# BMS_V3.net
KiCad netlist of a schematic drawn in Altium Designer
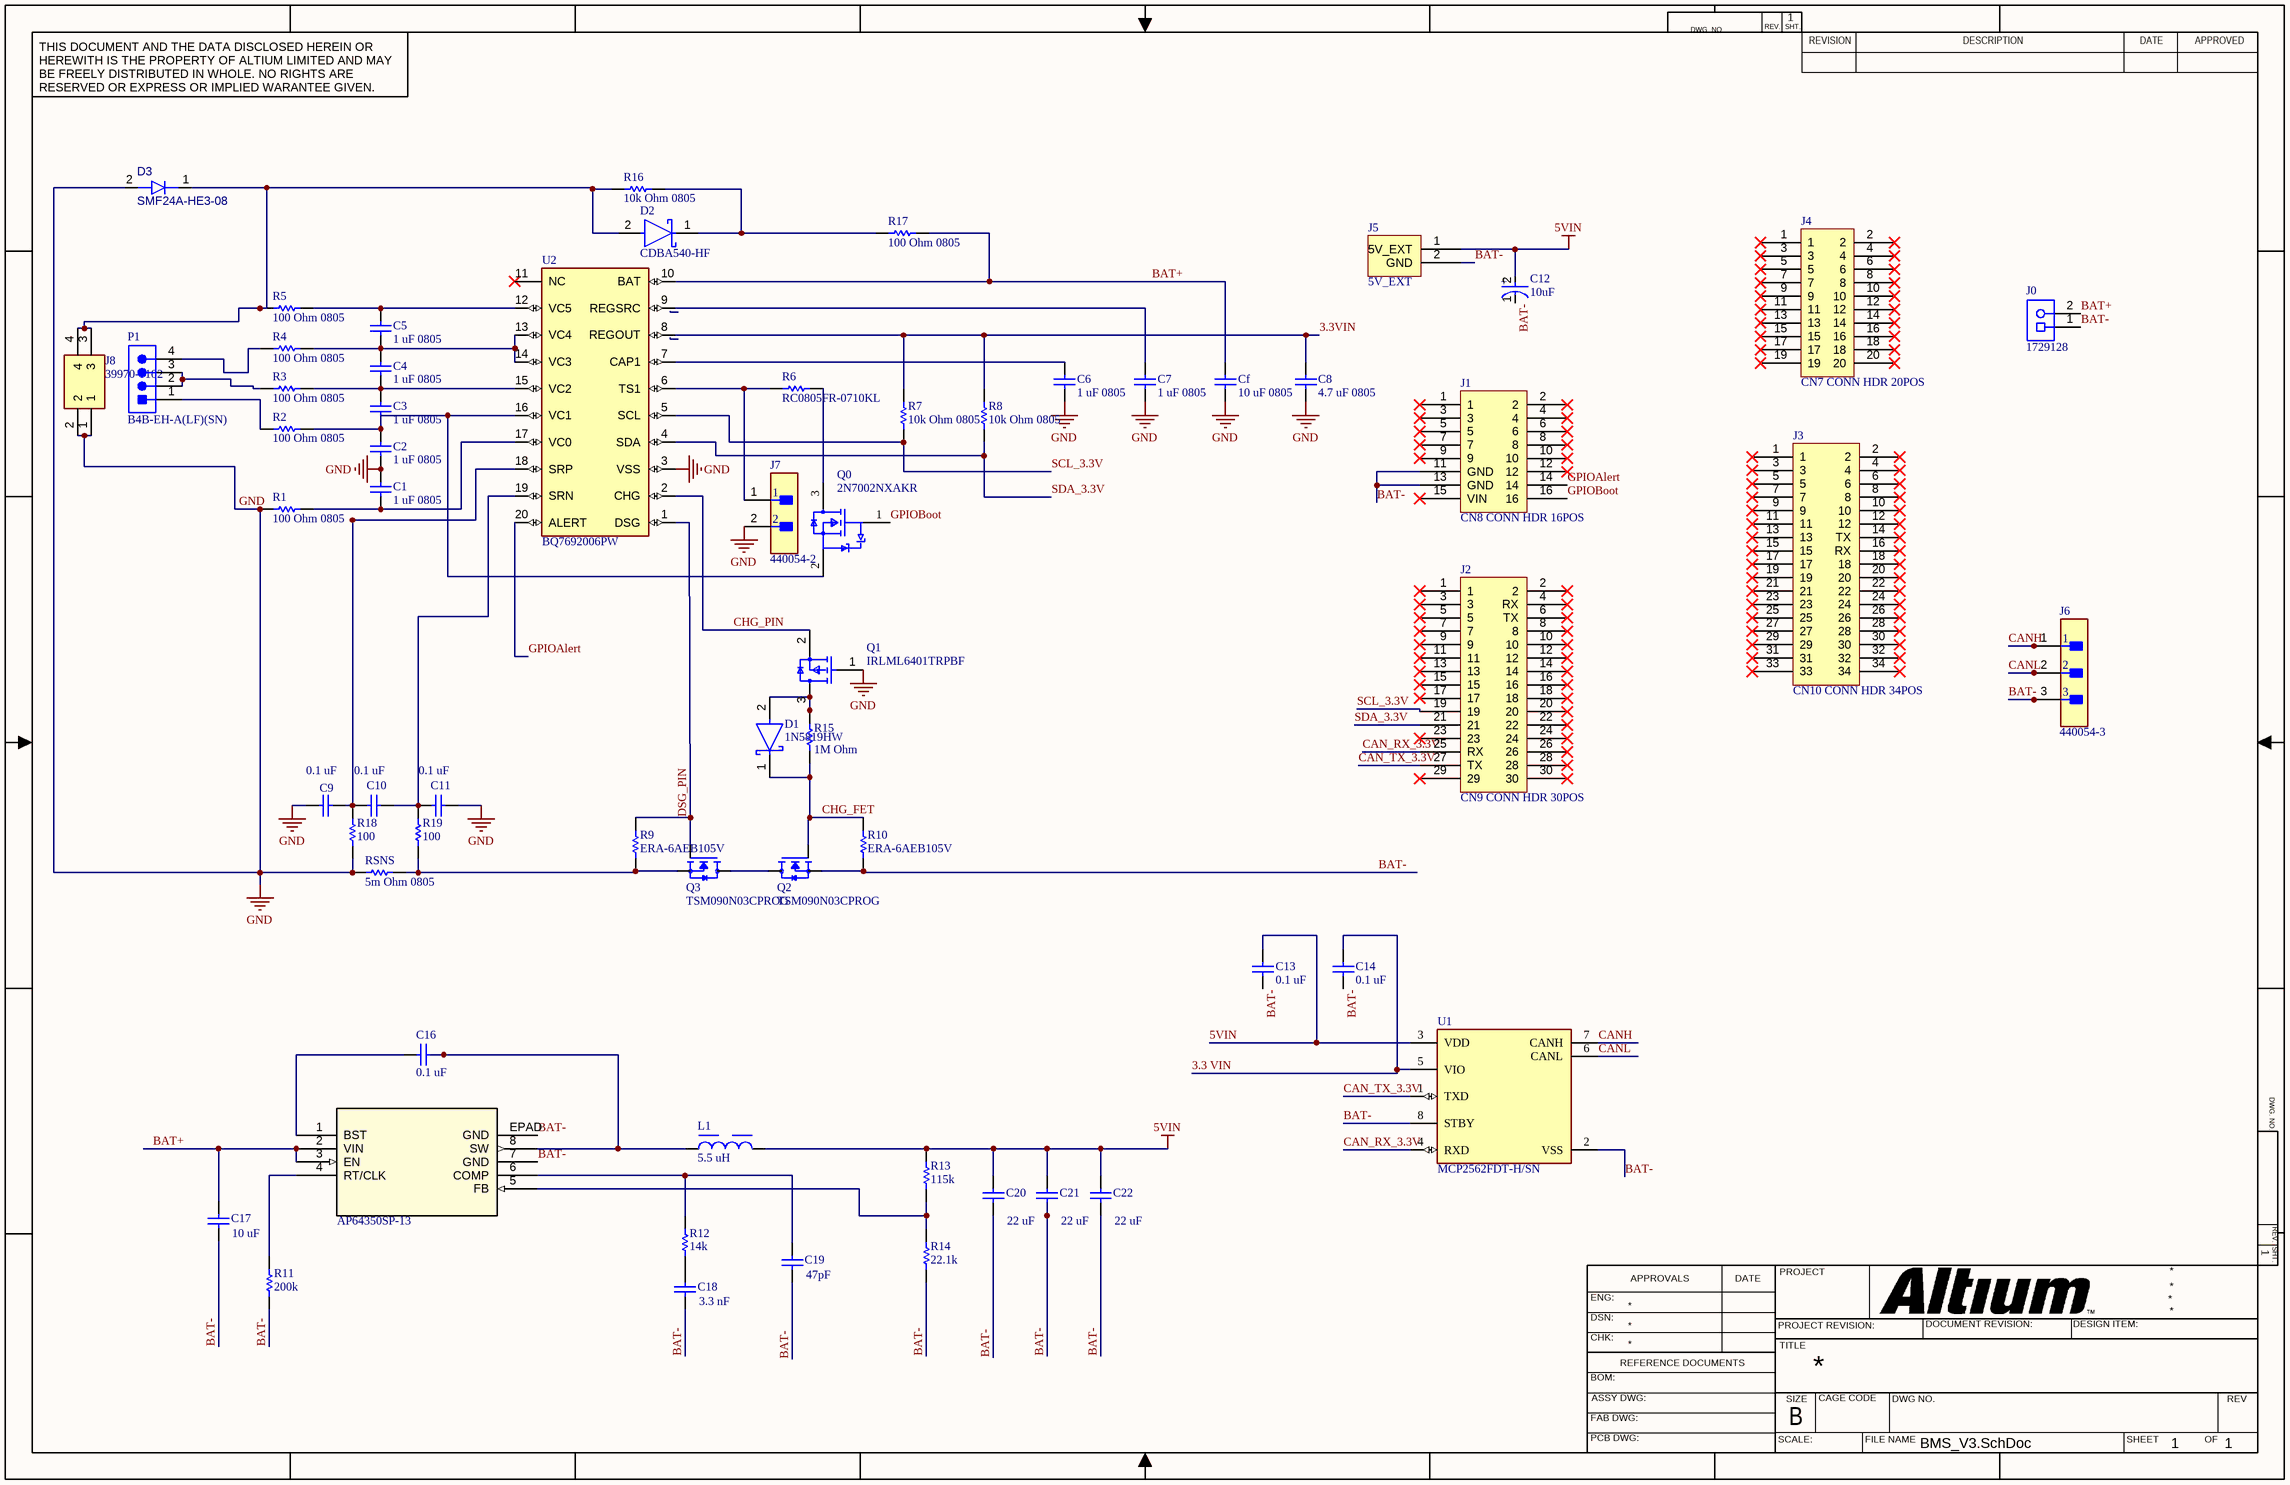
[diagram p0: BMS_V3.SchDoc]

(export (version "E")
  (design (tool "Eeschema 10.0.6"))
  (components
    (comp (ref "C1")
      (value "1 uF 0805")
      (footprint "CAPC2013X140X50LL20T25")
      (fields (field (name "PART NUMBER") "C0805C105K3RACTU") (field (name "MANUFACTURER") "Kemet"))
      (libsource (lib "Altium Content Vault") (part "CAP"))
    )
    (comp (ref "C2")
      (value "1 uF 0805")
      (footprint "CAPC2013X140X50LL20T25")
      (fields (field (name "PART NUMBER") "C0805C105K3RACTU") (field (name "MANUFACTURER") "Kemet"))
      (libsource (lib "Altium Content Vault") (part "CAP"))
    )
    (comp (ref "C3")
      (value "1 uF 0805")
      (footprint "CAPC2013X140X50LL20T25")
      (fields (field (name "PART NUMBER") "C0805C105K3RACTU") (field (name "MANUFACTURER") "Kemet"))
      (libsource (lib "Altium Content Vault") (part "CAP"))
    )
    (comp (ref "C4")
      (value "1 uF 0805")
      (footprint "CAPC2013X140X50LL20T25")
      (fields (field (name "PART NUMBER") "C0805C105K3RACTU") (field (name "MANUFACTURER") "Kemet"))
      (libsource (lib "Altium Content Vault") (part "CAP"))
    )
    (comp (ref "C5")
      (value "1 uF 0805")
      (footprint "CAPC2013X140X50LL20T25")
      (fields (field (name "PART NUMBER") "C0805C105K3RACTU") (field (name "MANUFACTURER") "Kemet"))
      (libsource (lib "Altium Content Vault") (part "CAP"))
    )
    (comp (ref "C6")
      (value "1 uF 0805")
      (footprint "CAPC2013X140X50LL20T25")
      (fields (field (name "PART NUMBER") "C0805C105K3RACTU") (field (name "MANUFACTURER") "Kemet"))
      (libsource (lib "Altium Content Vault") (part "CAP"))
    )
    (comp (ref "C7")
      (value "1 uF 0805")
      (footprint "CAPC2013X140X50LL20T25")
      (fields (field (name "PART NUMBER") "C0805C105K3RACTU") (field (name "MANUFACTURER") "Kemet"))
      (libsource (lib "Altium Content Vault") (part "CAP"))
    )
    (comp (ref "C8")
      (value "4.7 uF 0805")
      (footprint "CAPC2013X140X50LL20T25")
      (fields (field (name "PART NUMBER") "C0805C105K3RACTU") (field (name "MANUFACTURER") "Kemet"))
      (libsource (lib "Altium Content Vault") (part "CAP"))
    )
    (comp (ref "C9")
      (value "0.1 uF")
      (footprint "CAPC2013X140X50LL20T25")
      (fields (field (name "PART NUMBER") "C0805C105K3RACTU") (field (name "MANUFACTURER") "Kemet"))
      (libsource (lib "Altium Content Vault") (part "CAP"))
    )
    (comp (ref "C10")
      (value "0.1 uF")
      (footprint "CAPC2013X140X50LL20T25")
      (fields (field (name "PART NUMBER") "C0805C105K3RACTU") (field (name "MANUFACTURER") "Kemet"))
      (libsource (lib "Altium Content Vault") (part "CAP"))
    )
    (comp (ref "C11")
      (value "0.1 uF")
      (footprint "CAPC2013X140X50LL20T25")
      (fields (field (name "MANUFACTURER") "Kemet"))
      (libsource (lib "Altium Content Vault") (part "CAP"))
    )
    (comp (ref "C12")
      (value "10uF")
      (footprint "FP-FKC-MFG")
      (description "CAP ALUM 10UF 20% 50V SMD")
      (fields (field (name "TOLERANCE") "20%") (field (name "VOLTAGE") "50V"))
      (libsource (lib "Altium Content Vault") (part "a00bbbee19879c290e62620ae7e47b1"))
    )
    (comp (ref "C13")
      (value "0.1 uF")
      (footprint "CAPC2013X135X45NL10T25")
      (description "Chip Capacitor, 4.7 uF, +/- 10%, 16 V, -55 to 85 degC, 0805 (2012 Metric), RoHS, Tape and Reel")
      (fields (field (name "TOLERANCE") "10%") (field (name "PARTNUMBER") "GRM21BR61C475KA88L"))
      (libsource (lib "Altium Content Vault") (part "CAP-NP-2"))
    )
    (comp (ref "C14")
      (value "0.1 uF")
      (footprint "CAPC2013X135X45NL10T25")
      (description "Chip Capacitor, 4.7 uF, +/- 10%, 16 V, -55 to 85 degC, 0805 (2012 Metric), RoHS, Tape and Reel")
      (fields (field (name "TOLERANCE") "10%") (field (name "PARTNUMBER") "GRM21BR61C475KA88L"))
      (libsource (lib "Altium Content Vault") (part "CAP-NP-2"))
    )
    (comp (ref "C16")
      (value "0.1 uF")
      (footprint "CAPC2013X135X45NL10T25")
      (description "Chip Capacitor, 4.7 uF, +/- 10%, 16 V, -55 to 85 degC, 0805 (2012 Metric), RoHS, Tape and Reel")
      (fields (field (name "TOLERANCE") "10%") (field (name "PARTNUMBER") "GRM21BR61C475KA88L"))
      (libsource (lib "Altium Content Vault") (part "CAP-NP-2"))
    )
    (comp (ref "C17")
      (value "10 uF")
      (footprint "CAPC2013X135X45NL10T25")
      (description "Chip Capacitor, 4.7 uF, +/- 10%, 16 V, -55 to 85 degC, 0805 (2012 Metric), RoHS, Tape and Reel")
      (fields (field (name "TOLERANCE") "10%") (field (name "PARTNUMBER") "GRM21BR61C475KA88L"))
      (libsource (lib "Altium Content Vault") (part "CAP-NP-2"))
    )
    (comp (ref "C18")
      (value "3.3 nF")
      (footprint "CAPC2013X135X45NL10T25")
      (description "Chip Capacitor, 4.7 uF, +/- 10%, 16 V, -55 to 85 degC, 0805 (2012 Metric), RoHS, Tape and Reel")
      (fields (field (name "TOLERANCE") "10%") (field (name "PARTNUMBER") "GRM21BR61C475KA88L"))
      (libsource (lib "Altium Content Vault") (part "CAP-NP-2"))
    )
    (comp (ref "C19")
      (value "47pF")
      (footprint "CAPC2013X135X45NL10T25")
      (description "Chip Capacitor, 4.7 uF, +/- 10%, 16 V, -55 to 85 degC, 0805 (2012 Metric), RoHS, Tape and Reel")
      (fields (field (name "TOLERANCE") "10%") (field (name "PARTNUMBER") "GRM21BR61C475KA88L"))
      (libsource (lib "Altium Content Vault") (part "CAP-NP-2"))
    )
    (comp (ref "C20")
      (value "22 uF")
      (footprint "CAPC2013X135X45NL10T25")
      (description "Chip Capacitor, 4.7 uF, +/- 10%, 16 V, -55 to 85 degC, 0805 (2012 Metric), RoHS, Tape and Reel")
      (fields (field (name "TOLERANCE") "10%") (field (name "PARTNUMBER") "GRM21BR61C475KA88L"))
      (libsource (lib "Altium Content Vault") (part "CAP-NP-2"))
    )
    (comp (ref "C21")
      (value "22 uF")
      (footprint "CAPC2013X135X45NL10T25")
      (description "Chip Capacitor, 4.7 uF, +/- 10%, 16 V, -55 to 85 degC, 0805 (2012 Metric), RoHS, Tape and Reel")
      (fields (field (name "TOLERANCE") "10%") (field (name "PARTNUMBER") "GRM21BR61C475KA88L"))
      (libsource (lib "Altium Content Vault") (part "CAP-NP-2"))
    )
    (comp (ref "C22")
      (value "22 uF")
      (footprint "CAPC2013X135X45NL10T25")
      (description "Chip Capacitor, 4.7 uF, +/- 10%, 16 V, -55 to 85 degC, 0805 (2012 Metric), RoHS, Tape and Reel")
      (fields (field (name "TOLERANCE") "10%") (field (name "PARTNUMBER") "GRM21BR61C475KA88L"))
      (libsource (lib "Altium Content Vault") (part "CAP-NP-2"))
    )
    (comp (ref "Cf")
      (value "10 uF 0805")
      (footprint "CAPC2013X140X50LL20T25")
      (fields (field (name "PART NUMBER") "C0805C105K3RACTU") (field (name "MANUFACTURER") "Kemet"))
      (libsource (lib "Altium Content Vault") (part "CAP"))
    )
    (comp (ref "D1")
      (value "1N5819HW")
      (footprint "FP-SOD123-IPC_A")
      (description "DIODE SCHOTTKY 40V 1A SOD123")
      (libsource (lib "Altium Content Vault") (part "1d6ec82d83fb6aee721767c19dac4b9"))
    )
    (comp (ref "D2")
      (value "CDBA540-HF")
      (footprint "FP-DO-214AC-MFG")
      (description "DIODE SCHOTTKY 40V 5A DO214AC")
      (fields
        (field (name "OCTOPART") "https://octopart.com/cdba540-hf-comchip-57839773")
        (field (name "MANUFACTURER") "Comchip")
      )
      (libsource (lib "Altium Content Vault") (part "1d6ec82d83fb6aee721767c19dac4b9"))
    )
    (comp (ref "D3")
      (value "SMF24A-HE3-08")
      (footprint "DIOM2818X11N")
      (description "Trans Voltage Suppressor Diode, 1000W, 24V V(RWM), Unidirectional, 1 Element, Silicon, DO-219AB")
      (libsource (lib "Dattu Hariharan") (part "DIODE-2"))
    )
    (comp (ref "J0")
      (value "1729128")
      (footprint "PHOE-1729128-2_V")
      (description "PCB Terminal Block, 13.5 A, 400 V, 2-Pin THD, RoHS, Bulk")
      (fields (field (name "MANUFACTURER") "Phoenix Contact"))
      (libsource (lib "Altium Content Vault") (part "CN-2P-F-R2"))
    )
    (comp (ref "J1")
      (value "CN8 CONN HDR 16POS")
      (footprint "CN8_8X2_PADS")
      (description "CN8 CONN HDR 16POS 0.1 STACK")
      (libsource (lib "Dattu Hariharan") (part "CN8 CONN HDR 16POS"))
    )
    (comp (ref "J2")
      (value "CN9 CONN HDR 30POS")
      (footprint "CN9_15X2_PADS")
      (description "CN9 CONN HDR 30 POS  0.1 STACK")
      (libsource (lib "Dattu Hariharan") (part "CN9 CONN HDR 30POS"))
    )
    (comp (ref "J3")
      (value "CN10 CONN HDR 34POS")
      (footprint "CN10_17X2_PADS")
      (description "CN10 CONN HDR 34 POS  0.1 STACK")
      (libsource (lib "Dattu Hariharan") (part "CN10 CONN HDR 34POS"))
    )
    (comp (ref "J4")
      (value "CN7 CONN HDR 20POS")
      (footprint "CN7_10X2_PADS")
      (description "CN7 CONN HDR 20 POS  0.1 STACK")
      (libsource (lib "Dattu Hariharan") (part "CN7 CONN HDR 20POS"))
    )
    (comp (ref "J5")
      (value "5V_EXT")
      (footprint "5V_EXT")
      (libsource (lib "Dattu Hariharan") (part "5V_EXT"))
    )
    (comp (ref "J6")
      (value "440054-3")
      (footprint "FP-440054-3-MFG")
      (description "CONN HEADER VERT 3POS 2MM")
      (fields
        (field (name "OCTOPART") "https://octopart.com/440054-3-te+connectivity-40394845")
        (field (name "MANUFACTURER") "TE Connectivity")
      )
      (libsource (lib "Altium Content Vault") (part "0d3f023dd272f625e17a2be33dea85f"))
    )
    (comp (ref "J7")
      (value "440054-2")
      (footprint "FP-440054-2-MFG")
      (description "CONN HEADER VERT 2POS 2MM")
      (fields
        (field (name "MANUFACTURER") "TE Connectivity")
        (field (name "OCTOPART") "https://octopart.com/440054-2-te+connectivity-40237927")
      )
      (libsource (lib "Altium Content Vault") (part "3bc925449376181038e59eaffc5286c"))
    )
    (comp (ref "J8")
      (value "39970-0102")
      (footprint "399700102:399700102")
      (description "10.16mm Beau Eurostyle Fixed Mount PCB Terminal Block, High Power 40A,  Circuits")
      (fields (field (name "MOUSER PART NUMBER") "538-39970-0102"))
      (libsource (lib "39970-0102") (part "39970-0102"))
    )
    (comp (ref "L1")
      (value "5.5 uH")
      (footprint "WE-HCI_1050")
      (fields (field (name "TOLERANCE") "20%"))
      (libsource (lib "Altium Content Vault") (part "Inductor - 3"))
    )
    (comp (ref "P1")
      (value "B4B-EH-A(LF)(SN)")
      (footprint "JST-B4B-EH-A_V")
      (fields (field (name "MANUFACTURER") "JST"))
      (libsource (lib "Altium Content Vault") (part "CN-1P-M-R4"))
    )
    (comp (ref "Q0")
      (value "2N7002NXAKR")
      (footprint "FP-SOT23-IPC_B")
      (description "2N7002NXAK/SOT23/TO-236AB")
      (libsource (lib "Altium Content Vault") (part "bf18956dcdab3ff4da62eb44f668dfe"))
    )
    (comp (ref "Q1")
      (value "IRLML6401TRPBF")
      (footprint "FP-SOT23-MFG")
      (description "MOSFET P-CH 12V 4.3A SOT-23")
      (fields
        (field (name "MANUFACTURER") "Infineon")
        (field (name "OCTOPART") "https://octopart.com/irlml6401trpbf-infineon-65874987")
      )
      (libsource (lib "Altium Content Vault") (part "28bfa747e7c25bfdd37193474a7f289"))
    )
    (comp (ref "Q2")
      (value "TSM090N03CPROG")
      (footprint "TRANS_TSM090N03CPROG")
      (description "N-Channel 30 V 50A (Tc) 40W (Tc) Surface Mount TO-252 (DPAK)")
      (fields (field (name "MF") "Taiwan Semiconductor"))
      (libsource (lib "Dattu Hariharan") (part "TSM090N03CPROG"))
    )
    (comp (ref "Q3")
      (value "TSM090N03CPROG")
      (footprint "TRANS_TSM090N03CPROG")
      (description "N-Channel 30 V 50A (Tc) 40W (Tc) Surface Mount TO-252 (DPAK)")
      (fields (field (name "MF") "Taiwan Semiconductor"))
      (libsource (lib "Dattu Hariharan") (part "TSM090N03CPROG"))
    )
    (comp (ref "R1")
      (value "100 Ohm 0805")
      (footprint "RESC2013X60X30ML20T20")
      (fields (field (name "PART NUMBER") "RK73H2ATTD1000F") (field (name "MANUFACTURER") "KOA Speer"))
      (libsource (lib "Altium Content Vault") (part "RES"))
    )
    (comp (ref "R2")
      (value "100 Ohm 0805")
      (footprint "RESC2013X60X30ML20T20")
      (fields (field (name "PART NUMBER") "RK73H2ATTD1000F") (field (name "MANUFACTURER") "KOA Speer"))
      (libsource (lib "Altium Content Vault") (part "RES"))
    )
    (comp (ref "R3")
      (value "100 Ohm 0805")
      (footprint "RESC2013X60X30ML20T20")
      (fields (field (name "PART NUMBER") "RK73H2ATTD1000F") (field (name "MANUFACTURER") "KOA Speer"))
      (libsource (lib "Altium Content Vault") (part "RES"))
    )
    (comp (ref "R4")
      (value "100 Ohm 0805")
      (footprint "RESC2013X60X30ML20T20")
      (fields (field (name "PART NUMBER") "RK73H2ATTD1000F") (field (name "MANUFACTURER") "KOA Speer"))
      (libsource (lib "Altium Content Vault") (part "RES"))
    )
    (comp (ref "R5")
      (value "100 Ohm 0805")
      (footprint "RESC2013X60X30ML20T20")
      (fields (field (name "PART NUMBER") "RK73H2ATTD1000F") (field (name "MANUFACTURER") "KOA Speer"))
      (libsource (lib "Altium Content Vault") (part "RES"))
    )
    (comp (ref "R6")
      (value "RC0805FR-0710KL")
      (footprint "RESC2013X60X35NL10T20")
      (description "Chip Resistor, 10 KOhm, +/- 1%, 0.125 W, -55 to 155 degC, 0805 (2012 Metric), RoHS, Tape and Reel")
      (fields (field (name "MANUFACTURER") "Yageo"))
      (libsource (lib "Altium Content Vault") (part "RES-2"))
    )
    (comp (ref "R7")
      (value "10k Ohm 0805")
      (footprint "RESC2013X60X30ML20T20")
      (fields (field (name "PART NUMBER") "RK73H2ATTD1000F") (field (name "MANUFACTURER") "KOA Speer"))
      (libsource (lib "Altium Content Vault") (part "RES"))
    )
    (comp (ref "R8")
      (value "10k Ohm 0805")
      (footprint "RESC2013X60X30ML20T20")
      (fields (field (name "PART NUMBER") "RK73H2ATTD1000F") (field (name "MANUFACTURER") "KOA Speer"))
      (libsource (lib "Altium Content Vault") (part "RES"))
    )
    (comp (ref "R9")
      (value "ERA-6AEB105V")
      (footprint "RESC2013X60X40LL20T25")
      (fields (field (name "MANUFACTURER") "Panasonic"))
      (libsource (lib "Altium Content Vault") (part "RES"))
    )
    (comp (ref "R10")
      (value "ERA-6AEB105V")
      (footprint "RESC2013X60X40LL20T25")
      (fields (field (name "MANUFACTURER") "Panasonic"))
      (libsource (lib "Altium Content Vault") (part "RES"))
    )
    (comp (ref "R11")
      (value "200k")
      (footprint "RESC2013X60X35ML10T20")
      (description "Chip Resistor, 1 KOhm, +/- 1%, 125 mW, -55 to 155 degC, 0805 (2012 Metric), RoHS, Tape and Reel")
      (fields (field (name "TOLERANCE") "1%") (field (name "MANUFACTURER") "Yageo"))
      (libsource (lib "Altium Content Vault") (part "RES-2"))
    )
    (comp (ref "R12")
      (value "14k")
      (footprint "RESC2013X60X35ML10T20")
      (description "Chip Resistor, 1 KOhm, +/- 1%, 125 mW, -55 to 155 degC, 0805 (2012 Metric), RoHS, Tape and Reel")
      (fields (field (name "TOLERANCE") "1%") (field (name "MANUFACTURER") "Yageo"))
      (libsource (lib "Altium Content Vault") (part "RES-2"))
    )
    (comp (ref "R13")
      (value "115k")
      (footprint "RESC2013X60X35ML10T20")
      (description "Chip Resistor, 1 KOhm, +/- 1%, 125 mW, -55 to 155 degC, 0805 (2012 Metric), RoHS, Tape and Reel")
      (fields (field (name "TOLERANCE") "1%") (field (name "MANUFACTURER") "Yageo"))
      (libsource (lib "Altium Content Vault") (part "RES-2"))
    )
    (comp (ref "R14")
      (value "22.1k")
      (footprint "RESC2013X60X35ML10T20")
      (description "Chip Resistor, 1 KOhm, +/- 1%, 125 mW, -55 to 155 degC, 0805 (2012 Metric), RoHS, Tape and Reel")
      (fields (field (name "TOLERANCE") "1%") (field (name "MANUFACTURER") "Yageo"))
      (libsource (lib "Altium Content Vault") (part "RES-2"))
    )
    (comp (ref "R15")
      (value "1M Ohm")
      (footprint "RESC2013X60X40LL20T25")
      (fields (field (name "PART NUMBER") "ERA-6AEB105V") (field (name "MANUFACTURER") "Panasonic"))
      (libsource (lib "Altium Content Vault") (part "RES"))
    )
    (comp (ref "R16")
      (value "10k Ohm 0805")
      (footprint "RESC2013X60X30ML20T20")
      (fields (field (name "PART NUMBER") "RK73H2ATTD1000F") (field (name "MANUFACTURER") "KOA Speer"))
      (libsource (lib "Altium Content Vault") (part "RES"))
    )
    (comp (ref "R17")
      (value "100 Ohm 0805")
      (footprint "RESC2013X60X30ML20T20")
      (fields (field (name "PART NUMBER") "RK73H2ATTD1000F") (field (name "MANUFACTURER") "KOA Speer"))
      (libsource (lib "Altium Content Vault") (part "RES"))
    )
    (comp (ref "R18")
      (value "100")
      (footprint "RESC2013X50X30LL20T20")
      (fields (field (name "MANUFACTURER") "Vishay Dale") (field (name "PART NUMBER") "CRCW0805100RFKEA"))
      (libsource (lib "Altium Content Vault") (part "RES"))
    )
    (comp (ref "R19")
      (value "100")
      (footprint "RESC2013X50X30LL20T20")
      (fields (field (name "MANUFACTURER") "Vishay Dale") (field (name "PART NUMBER") "CRCW0805100RFKEA"))
      (libsource (lib "Altium Content Vault") (part "RES"))
    )
    (comp (ref "RSNS")
      (value "5m Ohm 0805")
      (footprint "RESC2013X60X30ML20T20")
      (fields (field (name "PART NUMBER") "RK73H2ATTD1000F") (field (name "MANUFACTURER") "KOA Speer"))
      (libsource (lib "Altium Content Vault") (part "RES"))
    )
    (comp (ref "U1")
      (value "MCP2562FDT-H/SN")
      (footprint "FP-C04-057-SN-IPC_A")
      (description "IC TRANSCEIVER 1/1 8SOIC")
      (libsource (lib "Altium Content Vault") (part "d4eccbb03d796c5d2cef85367bb866b"))
    )
    (comp (ref "U2")
      (value "BQ7692006PW")
      (footprint "BQ7692006PW")
      (description "3 to 5-Series Cell Li-Ion and Li-Phosphate Battery Monitor (bq76940 Family)")
      (fields (field (name "MF") "Texas Instruments"))
      (libsource (lib "Dattu Hariharan") (part "BQ7692006PW"))
    )
    (comp (ref "U3")
      (value "AP64350SP-13")
      (footprint "SO-8EP_DIO")
      (description "No Description Available")
      (libsource (lib "Dattu Hariharan") (part "AP64350SP-13"))
    )
  )
  (nets
    (net (code "1") (name "/3.3 VIN") (class "Default")
      (node (ref "C14") (pin "2") (pinfunction "2_2") (pintype "passive"))
      (node (ref "U1") (pin "5") (pinfunction "VIO_5") (pintype "power_in"))
    )
    (net (code "2") (name "/3.3VIN") (class "Default")
      (node (ref "C8") (pin "2") (pinfunction "2_2") (pintype "passive"))
      (node (ref "R7") (pin "2") (pinfunction "2_2") (pintype "passive"))
      (node (ref "R8") (pin "2") (pinfunction "2_2") (pintype "passive"))
      (node (ref "U2") (pin "8") (pinfunction "REGOUT_8") (pintype "bidirectional"))
    )
    (net (code "4") (name "/BAT+") (class "Default")
      (node (ref "C17") (pin "2") (pinfunction "2_2") (pintype "passive"))
      (node (ref "Cf") (pin "2") (pinfunction "2_2") (pintype "passive"))
      (node (ref "J0") (pin "2") (pinfunction "2_2") (pintype "passive"))
      (node (ref "R17") (pin "2") (pinfunction "2_2") (pintype "passive"))
      (node (ref "U2") (pin "10") (pinfunction "BAT_10") (pintype "bidirectional"))
      (node (ref "U3") (pin "2") (pinfunction "VIN_2") (pintype "power_in"))
      (node (ref "U3") (pin "3") (pinfunction "EN_3") (pintype "input"))
    )
    (net (code "5") (name "/BAT-") (class "Default")
      (node (ref "C12") (pin "1") (pinfunction "C_1") (pintype "passive"))
      (node (ref "C13") (pin "1") (pinfunction "1_1") (pintype "passive"))
      (node (ref "C14") (pin "1") (pinfunction "1_1") (pintype "passive"))
      (node (ref "C17") (pin "1") (pinfunction "1_1") (pintype "passive"))
      (node (ref "C18") (pin "1") (pinfunction "1_1") (pintype "passive"))
      (node (ref "C19") (pin "1") (pinfunction "1_1") (pintype "passive"))
      (node (ref "C20") (pin "1") (pinfunction "1_1") (pintype "passive"))
      (node (ref "C21") (pin "1") (pinfunction "1_1") (pintype "passive"))
      (node (ref "C22") (pin "1") (pinfunction "1_1") (pintype "passive"))
      (node (ref "J0") (pin "1") (pinfunction "1_1") (pintype "passive"))
      (node (ref "J1") (pin "11") (pinfunction "GND_11") (pintype "passive"))
      (node (ref "J1") (pin "13") (pinfunction "GND_13") (pintype "passive"))
      (node (ref "J5") (pin "2") (pinfunction "GND_2") (pintype "passive"))
      (node (ref "J6") (pin "3") (pinfunction "3_3") (pintype "passive"))
      (node (ref "Q2") (pin "3") (pinfunction "S_3") (pintype "passive"))
      (node (ref "R10") (pin "1") (pinfunction "1_1") (pintype "passive"))
      (node (ref "R11") (pin "1") (pinfunction "1_1") (pintype "passive"))
      (node (ref "R14") (pin "1") (pinfunction "1_1") (pintype "passive"))
      (node (ref "U1") (pin "2") (pinfunction "VSS_2") (pintype "power_in"))
      (node (ref "U1") (pin "8") (pinfunction "STBY_8") (pintype "passive"))
      (node (ref "U3") (pin "7") (pinfunction "GND_7") (pintype "power_in"))
      (node (ref "U3") (pin "EPAD") (pinfunction "GND_EPAD") (pintype "power_in"))
    )
    (net (code "6") (name "/CANH") (class "Default")
      (node (ref "J6") (pin "1") (pinfunction "1_1") (pintype "passive"))
      (node (ref "U1") (pin "7") (pinfunction "CANH_7") (pintype "passive"))
    )
    (net (code "7") (name "/CANL") (class "Default")
      (node (ref "J6") (pin "2") (pinfunction "2_2") (pintype "passive"))
      (node (ref "U1") (pin "6") (pinfunction "CANL_6") (pintype "passive"))
    )
    (net (code "8") (name "/CAN_RX_3.3V") (class "Default")
      (node (ref "J2") (pin "25") (pinfunction "RX_25") (pintype "passive"))
      (node (ref "U1") (pin "4") (pinfunction "RXD_4") (pintype "bidirectional"))
    )
    (net (code "9") (name "/CAN_TX_3.3V") (class "Default")
      (node (ref "J2") (pin "27") (pinfunction "TX_27") (pintype "passive"))
      (node (ref "U1") (pin "1") (pinfunction "TXD_1") (pintype "bidirectional"))
    )
    (net (code "10") (name "/CHG_FET") (class "Default")
      (node (ref "D1") (pin "1") (pinfunction "C_1") (pintype "passive"))
      (node (ref "Q2") (pin "1") (pinfunction "G_1") (pintype "passive"))
      (node (ref "R10") (pin "2") (pinfunction "2_2") (pintype "passive"))
      (node (ref "R15") (pin "1") (pinfunction "1_1") (pintype "passive"))
    )
    (net (code "11") (name "/CHG_PIN") (class "Default")
      (node (ref "Q1") (pin "2") (pinfunction "S_2") (pintype "passive"))
      (node (ref "U2") (pin "2") (pinfunction "CHG_2") (pintype "bidirectional"))
    )
    (net (code "12") (name "/DSG_PIN") (class "Default")
      (node (ref "Q3") (pin "1") (pinfunction "G_1") (pintype "passive"))
      (node (ref "R9") (pin "2") (pinfunction "2_2") (pintype "passive"))
      (node (ref "U2") (pin "1") (pinfunction "DSG_1") (pintype "bidirectional"))
    )
    (net (code "13") (name "/GPIOAlert") (class "Default")
      (node (ref "J1") (pin "14") (pinfunction "14_14") (pintype "passive"))
      (node (ref "U2") (pin "20") (pinfunction "ALERT_20") (pintype "bidirectional"))
    )
    (net (code "14") (name "/GPIOBoot") (class "Default")
      (node (ref "J1") (pin "16") (pinfunction "16_16") (pintype "passive"))
      (node (ref "Q0") (pin "1") (pinfunction "G_1") (pintype "passive"))
    )
    (net (code "15") (name "/SCL_3.3V") (class "Default")
      (node (ref "J2") (pin "19") (pinfunction "19_19") (pintype "passive"))
      (node (ref "R7") (pin "1") (pinfunction "1_1") (pintype "passive"))
      (node (ref "U2") (pin "5") (pinfunction "SCL_5") (pintype "bidirectional"))
    )
    (net (code "16") (name "/SDA_3.3V") (class "Default")
      (node (ref "J2") (pin "21") (pinfunction "21_21") (pintype "passive"))
      (node (ref "R8") (pin "1") (pinfunction "1_1") (pintype "passive"))
      (node (ref "U2") (pin "4") (pinfunction "SDA_4") (pintype "bidirectional"))
    )
    (net (code "17") (name "5VIN") (class "Default")
      (node (ref "C12") (pin "2") (pinfunction "A_2") (pintype "passive"))
      (node (ref "C13") (pin "2") (pinfunction "2_2") (pintype "passive"))
      (node (ref "C20") (pin "2") (pinfunction "2_2") (pintype "passive"))
      (node (ref "C21") (pin "2") (pinfunction "2_2") (pintype "passive"))
      (node (ref "C22") (pin "2") (pinfunction "2_2") (pintype "passive"))
      (node (ref "J5") (pin "1") (pinfunction "5V_EXT_1") (pintype "passive"))
      (node (ref "L1") (pin "2") (pinfunction "2_2") (pintype "passive"))
      (node (ref "R13") (pin "2") (pinfunction "2_2") (pintype "passive"))
      (node (ref "U1") (pin "3") (pinfunction "VDD_3") (pintype "power_in"))
    )
    (net (code "18") (name "GND") (class "Default")
      (node (ref "C1") (pin "2") (pinfunction "2_2") (pintype "passive"))
      (node (ref "C11") (pin "1") (pinfunction "1_1") (pintype "passive"))
      (node (ref "C2") (pin "1") (pinfunction "1_1") (pintype "passive"))
      (node (ref "C6") (pin "1") (pinfunction "1_1") (pintype "passive"))
      (node (ref "C7") (pin "1") (pinfunction "1_1") (pintype "passive"))
      (node (ref "C8") (pin "1") (pinfunction "1_1") (pintype "passive"))
      (node (ref "C9") (pin "2") (pinfunction "2_2") (pintype "passive"))
      (node (ref "Cf") (pin "1") (pinfunction "1_1") (pintype "passive"))
      (node (ref "D3") (pin "2") (pinfunction "A_2") (pintype "passive"))
      (node (ref "J7") (pin "2") (pinfunction "2_2") (pintype "passive"))
      (node (ref "J8") (pin "1") (pinfunction "1_1") (pintype "passive"))
      (node (ref "J8") (pin "2") (pinfunction "2_2") (pintype "passive"))
      (node (ref "Q1") (pin "1") (pinfunction "G_1") (pintype "passive"))
      (node (ref "R1") (pin "1") (pinfunction "1_1") (pintype "passive"))
      (node (ref "R18") (pin "1") (pinfunction "1_1") (pintype "passive"))
      (node (ref "RSNS") (pin "2") (pinfunction "2_2") (pintype "passive"))
      (node (ref "U2") (pin "3") (pinfunction "VSS_3") (pintype "bidirectional"))
    )
    (net (code "19") (name "Net-(C18-Pad2)") (class "Default")
      (node (ref "C18") (pin "2") (pinfunction "2_2") (pintype "passive"))
      (node (ref "R12") (pin "1") (pinfunction "1_1") (pintype "passive"))
    )
    (net (code "20") (name "Net-(D1-A)") (class "Default")
      (node (ref "D1") (pin "2") (pinfunction "A_2") (pintype "passive"))
      (node (ref "Q1") (pin "3") (pinfunction "D_3") (pintype "passive"))
      (node (ref "R15") (pin "2") (pinfunction "2_2") (pintype "passive"))
    )
    (net (code "21") (name "Net-(D2-A)") (class "Default")
      (node (ref "D2") (pin "2") (pinfunction "A_2") (pintype "passive"))
      (node (ref "D3") (pin "1") (pinfunction "K_1") (pintype "passive"))
      (node (ref "J8") (pin "3") (pinfunction "3_3") (pintype "passive"))
      (node (ref "J8") (pin "4") (pinfunction "4_4") (pintype "passive"))
      (node (ref "R16") (pin "1") (pinfunction "1_1") (pintype "passive"))
      (node (ref "R5") (pin "1") (pinfunction "1_1") (pintype "passive"))
    )
    (net (code "22") (name "Net-(D2-C)") (class "Default")
      (node (ref "D2") (pin "1") (pinfunction "C_1") (pintype "passive"))
      (node (ref "R16") (pin "2") (pinfunction "2_2") (pintype "passive"))
      (node (ref "R17") (pin "1") (pinfunction "1_1") (pintype "passive"))
    )
    (net (code "23") (name "Net-(P1-Pad1)") (class "Default")
      (node (ref "P1") (pin "1") (pinfunction "1_1") (pintype "passive"))
      (node (ref "R2") (pin "1") (pinfunction "1_1") (pintype "passive"))
    )
    (net (code "24") (name "Net-(P1-Pad2)") (class "Default")
      (node (ref "P1") (pin "2") (pinfunction "2_2") (pintype "passive"))
      (node (ref "P1") (pin "3") (pinfunction "3_3") (pintype "passive"))
      (node (ref "R3") (pin "1") (pinfunction "1_1") (pintype "passive"))
    )
    (net (code "25") (name "Net-(P1-Pad4)") (class "Default")
      (node (ref "P1") (pin "4") (pinfunction "4_4") (pintype "passive"))
      (node (ref "R4") (pin "1") (pinfunction "1_1") (pintype "passive"))
    )
    (net (code "26") (name "Net-(Q0-D)") (class "Default")
      (node (ref "Q0") (pin "3") (pinfunction "D_3") (pintype "passive"))
      (node (ref "R6") (pin "2") (pinfunction "2_2") (pintype "passive"))
    )
    (net (code "27") (name "Net-(Q0-S)") (class "Default")
      (node (ref "C2") (pin "2") (pinfunction "2_2") (pintype "passive"))
      (node (ref "C3") (pin "1") (pinfunction "1_1") (pintype "passive"))
      (node (ref "Q0") (pin "2") (pinfunction "S_2") (pintype "passive"))
      (node (ref "R2") (pin "2") (pinfunction "2_2") (pintype "passive"))
      (node (ref "U2") (pin "16") (pinfunction "VC1_16") (pintype "bidirectional"))
    )
    (net (code "28") (name "Net-(Q2-D)") (class "Default")
      (node (ref "Q2") (pin "2") (pinfunction "D_2") (pintype "passive"))
      (node (ref "Q3") (pin "2") (pinfunction "D_2") (pintype "passive"))
    )
    (net (code "29") (name "Net-(Q3-S)") (class "Default")
      (node (ref "Q3") (pin "3") (pinfunction "S_3") (pintype "passive"))
      (node (ref "R19") (pin "1") (pinfunction "1_1") (pintype "passive"))
      (node (ref "R9") (pin "1") (pinfunction "1_1") (pintype "passive"))
      (node (ref "RSNS") (pin "1") (pinfunction "1_1") (pintype "passive"))
    )
    (net (code "30") (name "Net-(U2-CAP1)") (class "Default")
      (node (ref "C6") (pin "2") (pinfunction "2_2") (pintype "passive"))
      (node (ref "U2") (pin "7") (pinfunction "CAP1_7") (pintype "bidirectional"))
    )
    (net (code "31") (name "Net-(U2-REGSRC)") (class "Default")
      (node (ref "C7") (pin "2") (pinfunction "2_2") (pintype "passive"))
      (node (ref "U2") (pin "9") (pinfunction "REGSRC_9") (pintype "bidirectional"))
    )
    (net (code "32") (name "Net-(U2-SRN)") (class "Default")
      (node (ref "C10") (pin "1") (pinfunction "1_1") (pintype "passive"))
      (node (ref "C11") (pin "2") (pinfunction "2_2") (pintype "passive"))
      (node (ref "R19") (pin "2") (pinfunction "2_2") (pintype "passive"))
      (node (ref "U2") (pin "19") (pinfunction "SRN_19") (pintype "bidirectional"))
    )
    (net (code "33") (name "Net-(U2-SRP)") (class "Default")
      (node (ref "C10") (pin "2") (pinfunction "2_2") (pintype "passive"))
      (node (ref "C9") (pin "1") (pinfunction "1_1") (pintype "passive"))
      (node (ref "R18") (pin "2") (pinfunction "2_2") (pintype "passive"))
      (node (ref "U2") (pin "18") (pinfunction "SRP_18") (pintype "bidirectional"))
    )
    (net (code "34") (name "Net-(U2-TS1)") (class "Default")
      (node (ref "J7") (pin "1") (pinfunction "1_1") (pintype "passive"))
      (node (ref "R6") (pin "1") (pinfunction "1_1") (pintype "passive"))
      (node (ref "U2") (pin "6") (pinfunction "TS1_6") (pintype "bidirectional"))
    )
    (net (code "35") (name "Net-(U2-VC0)") (class "Default")
      (node (ref "C1") (pin "1") (pinfunction "1_1") (pintype "passive"))
      (node (ref "R1") (pin "2") (pinfunction "2_2") (pintype "passive"))
      (node (ref "U2") (pin "17") (pinfunction "VC0_17") (pintype "bidirectional"))
    )
    (net (code "36") (name "Net-(U2-VC2)") (class "Default")
      (node (ref "C3") (pin "2") (pinfunction "2_2") (pintype "passive"))
      (node (ref "C4") (pin "1") (pinfunction "1_1") (pintype "passive"))
      (node (ref "R3") (pin "2") (pinfunction "2_2") (pintype "passive"))
      (node (ref "U2") (pin "15") (pinfunction "VC2_15") (pintype "bidirectional"))
    )
    (net (code "37") (name "Net-(U2-VC3)") (class "Default")
      (node (ref "C4") (pin "2") (pinfunction "2_2") (pintype "passive"))
      (node (ref "C5") (pin "1") (pinfunction "1_1") (pintype "passive"))
      (node (ref "R4") (pin "2") (pinfunction "2_2") (pintype "passive"))
      (node (ref "U2") (pin "13") (pinfunction "VC4_13") (pintype "bidirectional"))
      (node (ref "U2") (pin "14") (pinfunction "VC3_14") (pintype "bidirectional"))
    )
    (net (code "38") (name "Net-(U2-VC5)") (class "Default")
      (node (ref "C5") (pin "2") (pinfunction "2_2") (pintype "passive"))
      (node (ref "R5") (pin "2") (pinfunction "2_2") (pintype "passive"))
      (node (ref "U2") (pin "12") (pinfunction "VC5_12") (pintype "bidirectional"))
    )
    (net (code "39") (name "Net-(U3-BST)") (class "Default")
      (node (ref "C16") (pin "2") (pinfunction "2_2") (pintype "passive"))
      (node (ref "U3") (pin "1") (pinfunction "BST_1") (pintype "power_in"))
    )
    (net (code "40") (name "Net-(U3-COMP)") (class "Default")
      (node (ref "C19") (pin "2") (pinfunction "2_2") (pintype "passive"))
      (node (ref "R12") (pin "2") (pinfunction "2_2") (pintype "passive"))
      (node (ref "U3") (pin "6") (pinfunction "COMP_6") (pintype "passive"))
    )
    (net (code "41") (name "Net-(U3-FB)") (class "Default")
      (node (ref "R13") (pin "1") (pinfunction "1_1") (pintype "passive"))
      (node (ref "R14") (pin "2") (pinfunction "2_2") (pintype "passive"))
      (node (ref "U3") (pin "5") (pinfunction "FB_5") (pintype "input"))
    )
    (net (code "42") (name "Net-(U3-RT{slash}CLK)") (class "Default")
      (node (ref "R11") (pin "2") (pinfunction "2_2") (pintype "passive"))
      (node (ref "U3") (pin "4") (pinfunction "RT/CLK_4") (pintype "passive"))
    )
    (net (code "43") (name "Net-(U3-SW)") (class "Default")
      (node (ref "C16") (pin "1") (pinfunction "1_1") (pintype "passive"))
      (node (ref "L1") (pin "1") (pinfunction "1_1") (pintype "passive"))
      (node (ref "U3") (pin "8") (pinfunction "SW_8") (pintype "output"))
    )
    (net (code "44") (name "unconnected-(J1-Pad1)") (class "Default")
      (node (ref "J1") (pin "1") (pinfunction "1_1") (pintype "passive+no_connect"))
    )
    (net (code "45") (name "unconnected-(J1-Pad2)") (class "Default")
      (node (ref "J1") (pin "2") (pinfunction "2_2") (pintype "passive+no_connect"))
    )
    (net (code "46") (name "unconnected-(J1-Pad3)") (class "Default")
      (node (ref "J1") (pin "3") (pinfunction "3_3") (pintype "passive+no_connect"))
    )
    (net (code "47") (name "unconnected-(J1-Pad4)") (class "Default")
      (node (ref "J1") (pin "4") (pinfunction "4_4") (pintype "passive+no_connect"))
    )
    (net (code "48") (name "unconnected-(J1-Pad5)") (class "Default")
      (node (ref "J1") (pin "5") (pinfunction "5_5") (pintype "passive+no_connect"))
    )
    (net (code "49") (name "unconnected-(J1-Pad6)") (class "Default")
      (node (ref "J1") (pin "6") (pinfunction "6_6") (pintype "passive+no_connect"))
    )
    (net (code "50") (name "unconnected-(J1-Pad7)") (class "Default")
      (node (ref "J1") (pin "7") (pinfunction "7_7") (pintype "passive+no_connect"))
    )
    (net (code "51") (name "unconnected-(J1-Pad8)") (class "Default")
      (node (ref "J1") (pin "8") (pinfunction "8_8") (pintype "passive+no_connect"))
    )
    (net (code "52") (name "unconnected-(J1-Pad9)") (class "Default")
      (node (ref "J1") (pin "9") (pinfunction "9_9") (pintype "passive+no_connect"))
    )
    (net (code "53") (name "unconnected-(J1-Pad10)") (class "Default")
      (node (ref "J1") (pin "10") (pinfunction "10_10") (pintype "passive+no_connect"))
    )
    (net (code "54") (name "unconnected-(J1-Pad12)") (class "Default")
      (node (ref "J1") (pin "12") (pinfunction "12_12") (pintype "passive+no_connect"))
    )
    (net (code "55") (name "unconnected-(J1-VIN-Pad15)") (class "Default")
      (node (ref "J1") (pin "15") (pinfunction "VIN_15") (pintype "passive+no_connect"))
    )
    (net (code "56") (name "unconnected-(J2-Pad1)") (class "Default")
      (node (ref "J2") (pin "1") (pinfunction "1_1") (pintype "passive+no_connect"))
    )
    (net (code "57") (name "unconnected-(J2-Pad2)") (class "Default")
      (node (ref "J2") (pin "2") (pinfunction "2_2") (pintype "passive+no_connect"))
    )
    (net (code "58") (name "unconnected-(J2-Pad3)") (class "Default")
      (node (ref "J2") (pin "3") (pinfunction "3_3") (pintype "passive+no_connect"))
    )
    (net (code "59") (name "unconnected-(J2-Pad5)") (class "Default")
      (node (ref "J2") (pin "5") (pinfunction "5_5") (pintype "passive+no_connect"))
    )
    (net (code "60") (name "unconnected-(J2-Pad7)") (class "Default")
      (node (ref "J2") (pin "7") (pinfunction "7_7") (pintype "passive+no_connect"))
    )
    (net (code "61") (name "unconnected-(J2-Pad8)") (class "Default")
      (node (ref "J2") (pin "8") (pinfunction "8_8") (pintype "passive+no_connect"))
    )
    (net (code "62") (name "unconnected-(J2-Pad9)") (class "Default")
      (node (ref "J2") (pin "9") (pinfunction "9_9") (pintype "passive+no_connect"))
    )
    (net (code "63") (name "unconnected-(J2-Pad10)") (class "Default")
      (node (ref "J2") (pin "10") (pinfunction "10_10") (pintype "passive+no_connect"))
    )
    (net (code "64") (name "unconnected-(J2-Pad11)") (class "Default")
      (node (ref "J2") (pin "11") (pinfunction "11_11") (pintype "passive+no_connect"))
    )
    (net (code "65") (name "unconnected-(J2-Pad12)") (class "Default")
      (node (ref "J2") (pin "12") (pinfunction "12_12") (pintype "passive+no_connect"))
    )
    (net (code "66") (name "unconnected-(J2-Pad13)") (class "Default")
      (node (ref "J2") (pin "13") (pinfunction "13_13") (pintype "passive+no_connect"))
    )
    (net (code "67") (name "unconnected-(J2-Pad14)") (class "Default")
      (node (ref "J2") (pin "14") (pinfunction "14_14") (pintype "passive+no_connect"))
    )
    (net (code "68") (name "unconnected-(J2-Pad15)") (class "Default")
      (node (ref "J2") (pin "15") (pinfunction "15_15") (pintype "passive+no_connect"))
    )
    (net (code "69") (name "unconnected-(J2-Pad16)") (class "Default")
      (node (ref "J2") (pin "16") (pinfunction "16_16") (pintype "passive+no_connect"))
    )
    (net (code "70") (name "unconnected-(J2-Pad17)") (class "Default")
      (node (ref "J2") (pin "17") (pinfunction "17_17") (pintype "passive+no_connect"))
    )
    (net (code "71") (name "unconnected-(J2-Pad18)") (class "Default")
      (node (ref "J2") (pin "18") (pinfunction "18_18") (pintype "passive+no_connect"))
    )
    (net (code "72") (name "unconnected-(J2-Pad20)") (class "Default")
      (node (ref "J2") (pin "20") (pinfunction "20_20") (pintype "passive+no_connect"))
    )
    (net (code "73") (name "unconnected-(J2-Pad22)") (class "Default")
      (node (ref "J2") (pin "22") (pinfunction "22_22") (pintype "passive+no_connect"))
    )
    (net (code "74") (name "unconnected-(J2-Pad23)") (class "Default")
      (node (ref "J2") (pin "23") (pinfunction "23_23") (pintype "passive+no_connect"))
    )
    (net (code "75") (name "unconnected-(J2-Pad24)") (class "Default")
      (node (ref "J2") (pin "24") (pinfunction "24_24") (pintype "passive+no_connect"))
    )
    (net (code "76") (name "unconnected-(J2-Pad26)") (class "Default")
      (node (ref "J2") (pin "26") (pinfunction "26_26") (pintype "passive+no_connect"))
    )
    (net (code "77") (name "unconnected-(J2-Pad28)") (class "Default")
      (node (ref "J2") (pin "28") (pinfunction "28_28") (pintype "passive+no_connect"))
    )
    (net (code "78") (name "unconnected-(J2-Pad29)") (class "Default")
      (node (ref "J2") (pin "29") (pinfunction "29_29") (pintype "passive+no_connect"))
    )
    (net (code "79") (name "unconnected-(J2-Pad30)") (class "Default")
      (node (ref "J2") (pin "30") (pinfunction "30_30") (pintype "passive+no_connect"))
    )
    (net (code "80") (name "unconnected-(J2-RX-Pad4)") (class "Default")
      (node (ref "J2") (pin "4") (pinfunction "RX_4") (pintype "passive+no_connect"))
    )
    (net (code "81") (name "unconnected-(J2-TX-Pad6)") (class "Default")
      (node (ref "J2") (pin "6") (pinfunction "TX_6") (pintype "passive+no_connect"))
    )
    (net (code "82") (name "unconnected-(J3-Pad1)") (class "Default")
      (node (ref "J3") (pin "1") (pinfunction "1_1") (pintype "passive+no_connect"))
    )
    (net (code "83") (name "unconnected-(J3-Pad2)") (class "Default")
      (node (ref "J3") (pin "2") (pinfunction "2_2") (pintype "passive+no_connect"))
    )
    (net (code "84") (name "unconnected-(J3-Pad3)") (class "Default")
      (node (ref "J3") (pin "3") (pinfunction "3_3") (pintype "passive+no_connect"))
    )
    (net (code "85") (name "unconnected-(J3-Pad4)") (class "Default")
      (node (ref "J3") (pin "4") (pinfunction "4_4") (pintype "passive+no_connect"))
    )
    (net (code "86") (name "unconnected-(J3-Pad5)") (class "Default")
      (node (ref "J3") (pin "5") (pinfunction "5_5") (pintype "passive+no_connect"))
    )
    (net (code "87") (name "unconnected-(J3-Pad6)") (class "Default")
      (node (ref "J3") (pin "6") (pinfunction "6_6") (pintype "passive+no_connect"))
    )
    (net (code "88") (name "unconnected-(J3-Pad7)") (class "Default")
      (node (ref "J3") (pin "7") (pinfunction "7_7") (pintype "passive+no_connect"))
    )
    (net (code "89") (name "unconnected-(J3-Pad8)") (class "Default")
      (node (ref "J3") (pin "8") (pinfunction "8_8") (pintype "passive+no_connect"))
    )
    (net (code "90") (name "unconnected-(J3-Pad9)") (class "Default")
      (node (ref "J3") (pin "9") (pinfunction "9_9") (pintype "passive+no_connect"))
    )
    (net (code "91") (name "unconnected-(J3-Pad10)") (class "Default")
      (node (ref "J3") (pin "10") (pinfunction "10_10") (pintype "passive+no_connect"))
    )
    (net (code "92") (name "unconnected-(J3-Pad11)") (class "Default")
      (node (ref "J3") (pin "11") (pinfunction "11_11") (pintype "passive+no_connect"))
    )
    (net (code "93") (name "unconnected-(J3-Pad12)") (class "Default")
      (node (ref "J3") (pin "12") (pinfunction "12_12") (pintype "passive+no_connect"))
    )
    (net (code "94") (name "unconnected-(J3-Pad13)") (class "Default")
      (node (ref "J3") (pin "13") (pinfunction "13_13") (pintype "passive+no_connect"))
    )
    (net (code "95") (name "unconnected-(J3-Pad15)") (class "Default")
      (node (ref "J3") (pin "15") (pinfunction "15_15") (pintype "passive+no_connect"))
    )
    (net (code "96") (name "unconnected-(J3-Pad17)") (class "Default")
      (node (ref "J3") (pin "17") (pinfunction "17_17") (pintype "passive+no_connect"))
    )
    (net (code "97") (name "unconnected-(J3-Pad18)") (class "Default")
      (node (ref "J3") (pin "18") (pinfunction "18_18") (pintype "passive+no_connect"))
    )
    (net (code "98") (name "unconnected-(J3-Pad19)") (class "Default")
      (node (ref "J3") (pin "19") (pinfunction "19_19") (pintype "passive+no_connect"))
    )
    (net (code "99") (name "unconnected-(J3-Pad20)") (class "Default")
      (node (ref "J3") (pin "20") (pinfunction "20_20") (pintype "passive+no_connect"))
    )
    (net (code "100") (name "unconnected-(J3-Pad21)") (class "Default")
      (node (ref "J3") (pin "21") (pinfunction "21_21") (pintype "passive+no_connect"))
    )
    (net (code "101") (name "unconnected-(J3-Pad22)") (class "Default")
      (node (ref "J3") (pin "22") (pinfunction "22_22") (pintype "passive+no_connect"))
    )
    (net (code "102") (name "unconnected-(J3-Pad23)") (class "Default")
      (node (ref "J3") (pin "23") (pinfunction "23_23") (pintype "passive+no_connect"))
    )
    (net (code "103") (name "unconnected-(J3-Pad24)") (class "Default")
      (node (ref "J3") (pin "24") (pinfunction "24_24") (pintype "passive+no_connect"))
    )
    (net (code "104") (name "unconnected-(J3-Pad25)") (class "Default")
      (node (ref "J3") (pin "25") (pinfunction "25_25") (pintype "passive+no_connect"))
    )
    (net (code "105") (name "unconnected-(J3-Pad26)") (class "Default")
      (node (ref "J3") (pin "26") (pinfunction "26_26") (pintype "passive+no_connect"))
    )
    (net (code "106") (name "unconnected-(J3-Pad27)") (class "Default")
      (node (ref "J3") (pin "27") (pinfunction "27_27") (pintype "passive+no_connect"))
    )
    (net (code "107") (name "unconnected-(J3-Pad28)") (class "Default")
      (node (ref "J3") (pin "28") (pinfunction "28_28") (pintype "passive+no_connect"))
    )
    (net (code "108") (name "unconnected-(J3-Pad29)") (class "Default")
      (node (ref "J3") (pin "29") (pinfunction "29_29") (pintype "passive+no_connect"))
    )
    (net (code "109") (name "unconnected-(J3-Pad30)") (class "Default")
      (node (ref "J3") (pin "30") (pinfunction "30_30") (pintype "passive+no_connect"))
    )
    (net (code "110") (name "unconnected-(J3-Pad31)") (class "Default")
      (node (ref "J3") (pin "31") (pinfunction "31_31") (pintype "passive+no_connect"))
    )
    (net (code "111") (name "unconnected-(J3-Pad32)") (class "Default")
      (node (ref "J3") (pin "32") (pinfunction "32_32") (pintype "passive+no_connect"))
    )
    (net (code "112") (name "unconnected-(J3-Pad33)") (class "Default")
      (node (ref "J3") (pin "33") (pinfunction "33_33") (pintype "passive+no_connect"))
    )
    (net (code "113") (name "unconnected-(J3-Pad34)") (class "Default")
      (node (ref "J3") (pin "34") (pinfunction "34_34") (pintype "passive+no_connect"))
    )
    (net (code "114") (name "unconnected-(J3-RX-Pad16)") (class "Default")
      (node (ref "J3") (pin "16") (pinfunction "RX_16") (pintype "passive+no_connect"))
    )
    (net (code "115") (name "unconnected-(J3-TX-Pad14)") (class "Default")
      (node (ref "J3") (pin "14") (pinfunction "TX_14") (pintype "passive+no_connect"))
    )
    (net (code "116") (name "unconnected-(J4-Pad1)") (class "Default")
      (node (ref "J4") (pin "1") (pinfunction "1_1") (pintype "passive+no_connect"))
    )
    (net (code "117") (name "unconnected-(J4-Pad2)") (class "Default")
      (node (ref "J4") (pin "2") (pinfunction "2_2") (pintype "passive+no_connect"))
    )
    (net (code "118") (name "unconnected-(J4-Pad3)") (class "Default")
      (node (ref "J4") (pin "3") (pinfunction "3_3") (pintype "passive+no_connect"))
    )
    (net (code "119") (name "unconnected-(J4-Pad4)") (class "Default")
      (node (ref "J4") (pin "4") (pinfunction "4_4") (pintype "passive+no_connect"))
    )
    (net (code "120") (name "unconnected-(J4-Pad5)") (class "Default")
      (node (ref "J4") (pin "5") (pinfunction "5_5") (pintype "passive+no_connect"))
    )
    (net (code "121") (name "unconnected-(J4-Pad6)") (class "Default")
      (node (ref "J4") (pin "6") (pinfunction "6_6") (pintype "passive+no_connect"))
    )
    (net (code "122") (name "unconnected-(J4-Pad7)") (class "Default")
      (node (ref "J4") (pin "7") (pinfunction "7_7") (pintype "passive+no_connect"))
    )
    (net (code "123") (name "unconnected-(J4-Pad8)") (class "Default")
      (node (ref "J4") (pin "8") (pinfunction "8_8") (pintype "passive+no_connect"))
    )
    (net (code "124") (name "unconnected-(J4-Pad9)") (class "Default")
      (node (ref "J4") (pin "9") (pinfunction "9_9") (pintype "passive+no_connect"))
    )
    (net (code "125") (name "unconnected-(J4-Pad10)") (class "Default")
      (node (ref "J4") (pin "10") (pinfunction "10_10") (pintype "passive+no_connect"))
    )
    (net (code "126") (name "unconnected-(J4-Pad11)") (class "Default")
      (node (ref "J4") (pin "11") (pinfunction "11_11") (pintype "passive+no_connect"))
    )
    (net (code "127") (name "unconnected-(J4-Pad12)") (class "Default")
      (node (ref "J4") (pin "12") (pinfunction "12_12") (pintype "passive+no_connect"))
    )
    (net (code "128") (name "unconnected-(J4-Pad13)") (class "Default")
      (node (ref "J4") (pin "13") (pinfunction "13_13") (pintype "passive+no_connect"))
    )
    (net (code "129") (name "unconnected-(J4-Pad14)") (class "Default")
      (node (ref "J4") (pin "14") (pinfunction "14_14") (pintype "passive+no_connect"))
    )
    (net (code "130") (name "unconnected-(J4-Pad15)") (class "Default")
      (node (ref "J4") (pin "15") (pinfunction "15_15") (pintype "passive+no_connect"))
    )
    (net (code "131") (name "unconnected-(J4-Pad16)") (class "Default")
      (node (ref "J4") (pin "16") (pinfunction "16_16") (pintype "passive+no_connect"))
    )
    (net (code "132") (name "unconnected-(J4-Pad17)") (class "Default")
      (node (ref "J4") (pin "17") (pinfunction "17_17") (pintype "passive+no_connect"))
    )
    (net (code "133") (name "unconnected-(J4-Pad18)") (class "Default")
      (node (ref "J4") (pin "18") (pinfunction "18_18") (pintype "passive+no_connect"))
    )
    (net (code "134") (name "unconnected-(J4-Pad19)") (class "Default")
      (node (ref "J4") (pin "19") (pinfunction "19_19") (pintype "passive+no_connect"))
    )
    (net (code "135") (name "unconnected-(J4-Pad20)") (class "Default")
      (node (ref "J4") (pin "20") (pinfunction "20_20") (pintype "passive+no_connect"))
    )
    (net (code "136") (name "unconnected-(U2-NC-Pad11)") (class "Default")
      (node (ref "U2") (pin "11") (pinfunction "NC_11") (pintype "passive+no_connect"))
    )
  )
)
